# Main.net
KiCad netlist of a schematic drawn in EAGLE
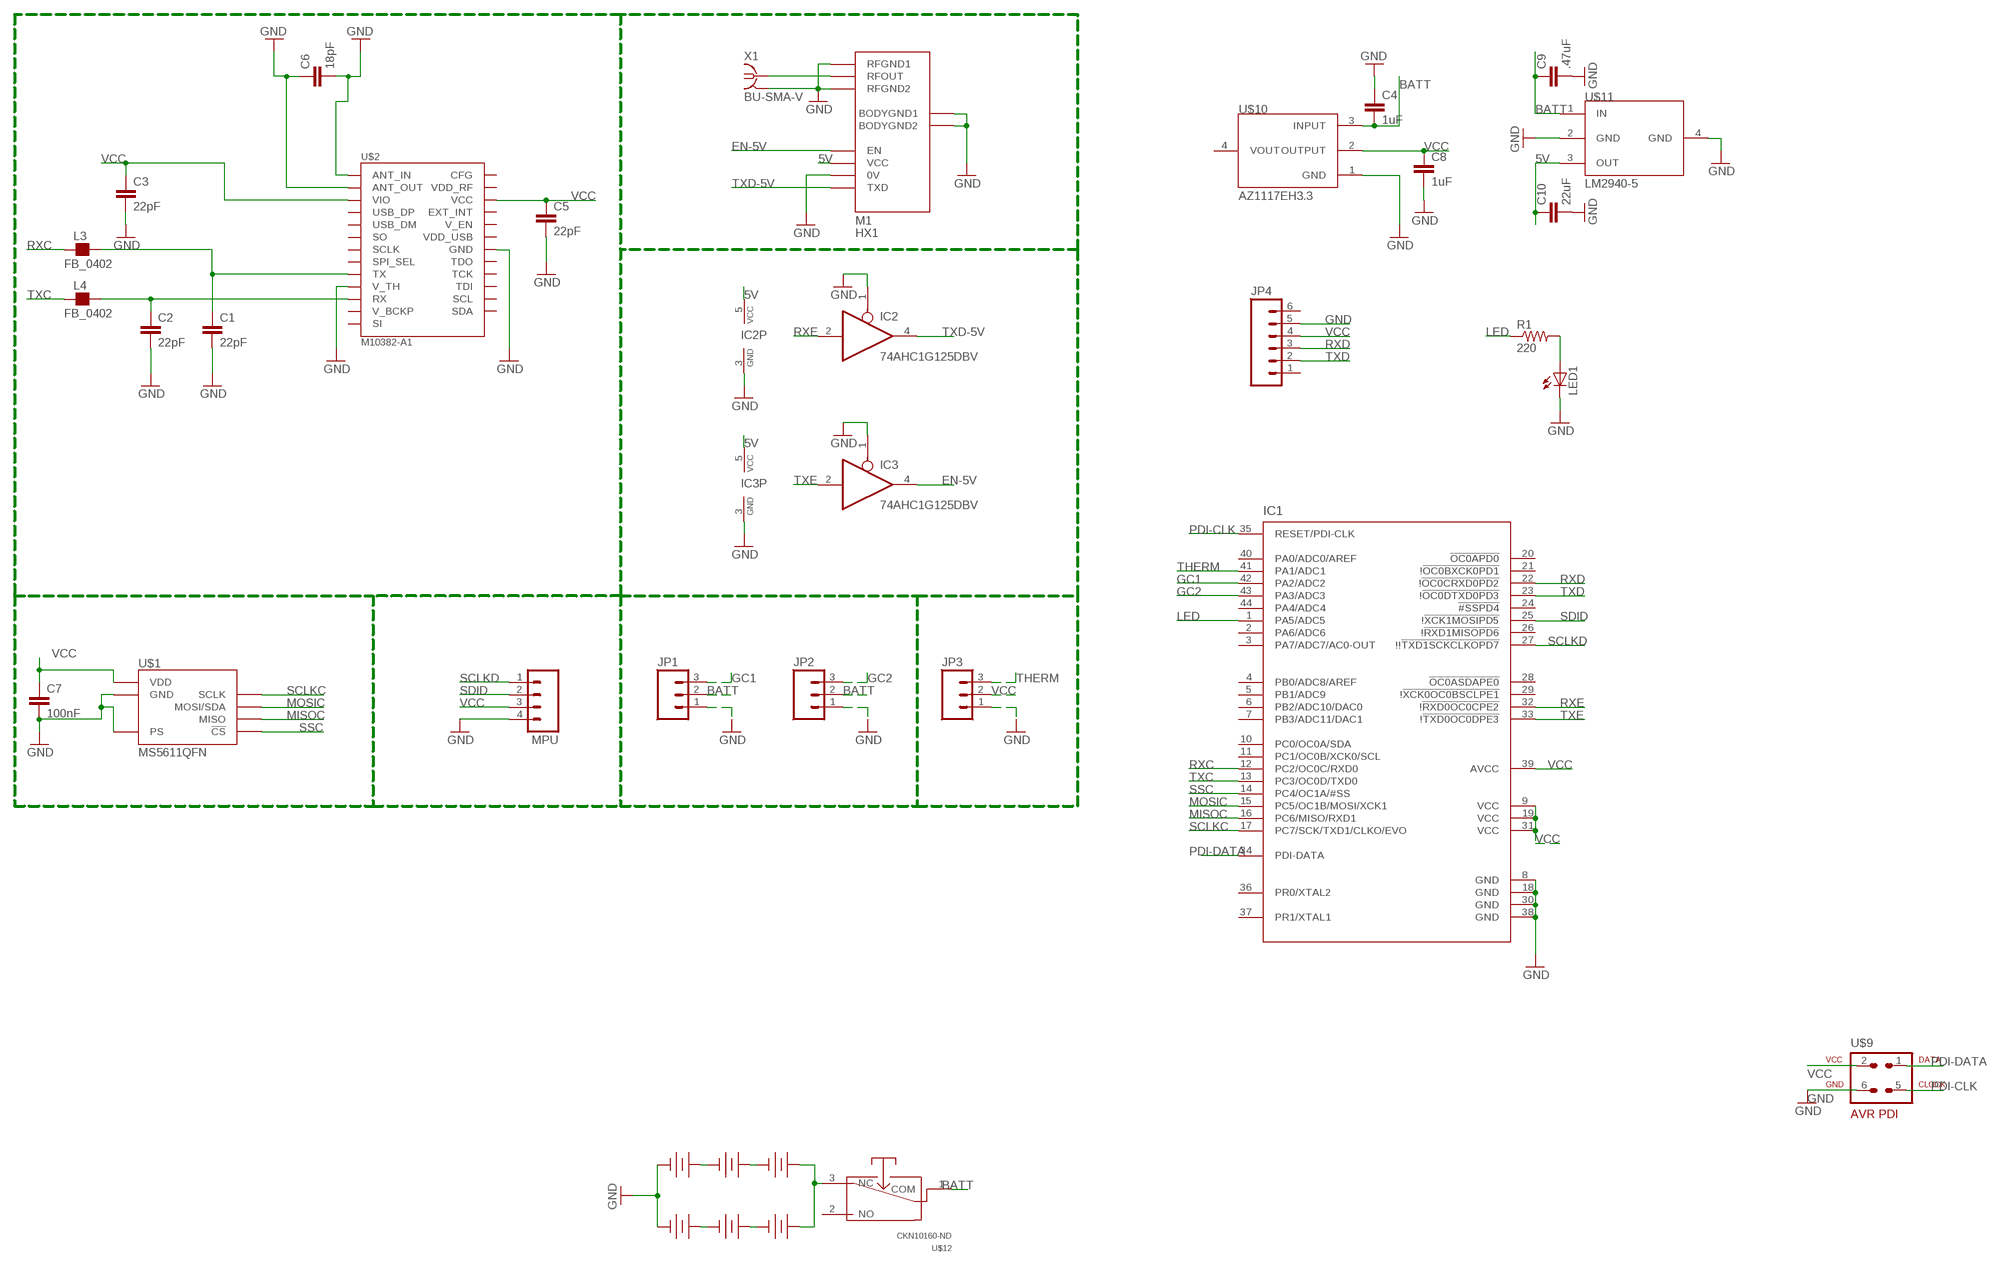
[diagram p0: schematic, sheet 1]

(export (version "E")
  (design (tool "Eeschema 10.0.6"))
  (components
    (comp (ref "C1")
      (value "22pF")
      (footprint "eagle-import:0805")
      (libsource (lib "eagle-import") (part "CAP0805"))
    )
    (comp (ref "C2")
      (value "22pF")
      (footprint "eagle-import:0805")
      (libsource (lib "eagle-import") (part "CAP0805"))
    )
    (comp (ref "C3")
      (value "22pF")
      (footprint "eagle-import:0805")
      (libsource (lib "eagle-import") (part "CAP0805"))
    )
    (comp (ref "C4")
      (value "1uF")
      (footprint "eagle-import:0603-CAP")
      (libsource (lib "eagle-import") (part "CAP0603-CAP"))
    )
    (comp (ref "C5")
      (value "22pF")
      (footprint "eagle-import:0805")
      (libsource (lib "eagle-import") (part "CAP0805"))
    )
    (comp (ref "C6")
      (value "18pF")
      (footprint "eagle-import:0805")
      (libsource (lib "eagle-import") (part "CAP0805"))
    )
    (comp (ref "C7")
      (value "100nF")
      (footprint "eagle-import:0805")
      (libsource (lib "eagle-import") (part "CAP0805"))
    )
    (comp (ref "C8")
      (value "1uF")
      (footprint "eagle-import:0603-CAP")
      (libsource (lib "eagle-import") (part "CAP0603-CAP"))
    )
    (comp (ref "C9")
      (value ".47uF")
      (footprint "eagle-import:0603-CAP")
      (libsource (lib "eagle-import") (part "CAP0603-CAP"))
    )
    (comp (ref "C10")
      (value "22uF")
      (footprint "eagle-import:0603-CAP")
      (libsource (lib "eagle-import") (part "CAP0603-CAP"))
    )
    (comp (ref "IC1")
      (value "AT-XMEGA-XXA4-AU")
      (footprint "eagle-import:QFP80P1200X1200X120-44N")
      (libsource (lib "eagle-import") (part "AT-XMEGA-XXA4-AU"))
    )
    (comp (ref "IC2")
      (value "74AHC1G125DBV")
      (footprint "eagle-import:SOT23-5")
      (libsource (lib "eagle-import") (part "741G125DBVAHC"))
    )
    (comp (ref "IC3")
      (value "74AHC1G125DBV")
      (footprint "eagle-import:SOT23-5")
      (libsource (lib "eagle-import") (part "741G125DBVAHC"))
    )
    (comp (ref "JP1")
      (value "M03JST-PTH")
      (footprint "eagle-import:JST-3-PTH")
      (libsource (lib "eagle-import") (part "M03JST-PTH"))
    )
    (comp (ref "JP2")
      (value "M03JST-PTH")
      (footprint "eagle-import:JST-3-PTH")
      (libsource (lib "eagle-import") (part "M03JST-PTH"))
    )
    (comp (ref "JP3")
      (value "M03JST-PTH")
      (footprint "eagle-import:JST-3-PTH")
      (libsource (lib "eagle-import") (part "M03JST-PTH"))
    )
    (comp (ref "JP4")
      (value "M06POLAR")
      (footprint "eagle-import:MOLEX-1X6")
      (libsource (lib "eagle-import") (part "M06POLAR"))
    )
    (comp (ref "L3")
      (value "FB_0402")
      (footprint "eagle-import:L0402")
      (libsource (lib "eagle-import") (part "FB_0402"))
    )
    (comp (ref "L4")
      (value "FB_0402")
      (footprint "eagle-import:L0402")
      (libsource (lib "eagle-import") (part "FB_0402"))
    )
    (comp (ref "LED1")
      (value "LEDCHIP-LED0603")
      (footprint "eagle-import:CHIP-LED0603")
      (libsource (lib "eagle-import") (part "LEDCHIP-LED0603"))
    )
    (comp (ref "M1")
      (value "HX1")
      (footprint "eagle-import:HX1")
      (libsource (lib "eagle-import") (part "HX1"))
    )
    (comp (ref "MPU")
      (value "M04")
      (footprint "eagle-import:04P")
      (libsource (lib "eagle-import") (part "M04"))
    )
    (comp (ref "R1")
      (value "220")
      (footprint "eagle-import:R0603")
      (libsource (lib "eagle-import") (part "R-US_R0603"))
    )
    (comp (ref "U$1")
      (value "MS5611QFN")
      (footprint "eagle-import:MS5611-01BA01")
      (libsource (lib "eagle-import") (part "MS5611QFN"))
    )
    (comp (ref "U$2")
      (value "M10382-A1")
      (footprint "eagle-import:M10382-A1")
      (libsource (lib "eagle-import") (part "M10382-A1"))
    )
    (comp (ref "U$3")
      (value "123_BATTERY_HOLDERCR-123-A")
      (footprint "eagle-import:CR-123-A_HOLDER")
      (libsource (lib "eagle-import") (part "123_BATTERY_HOLDERCR-123-A"))
    )
    (comp (ref "U$4")
      (value "123_BATTERY_HOLDERCR-123-A")
      (footprint "eagle-import:CR-123-A_HOLDER")
      (libsource (lib "eagle-import") (part "123_BATTERY_HOLDERCR-123-A"))
    )
    (comp (ref "U$5")
      (value "123_BATTERY_HOLDERCR-123-A")
      (footprint "eagle-import:CR-123-A_HOLDER")
      (libsource (lib "eagle-import") (part "123_BATTERY_HOLDERCR-123-A"))
    )
    (comp (ref "U$6")
      (value "123_BATTERY_HOLDERCR-123-A")
      (footprint "eagle-import:CR-123-A_HOLDER")
      (libsource (lib "eagle-import") (part "123_BATTERY_HOLDERCR-123-A"))
    )
    (comp (ref "U$7")
      (value "123_BATTERY_HOLDERCR-123-A")
      (footprint "eagle-import:CR-123-A_HOLDER")
      (libsource (lib "eagle-import") (part "123_BATTERY_HOLDERCR-123-A"))
    )
    (comp (ref "U$8")
      (value "123_BATTERY_HOLDERCR-123-A")
      (footprint "eagle-import:CR-123-A_HOLDER")
      (libsource (lib "eagle-import") (part "123_BATTERY_HOLDERCR-123-A"))
    )
    (comp (ref "U$9")
      (value "AVR-PDIVERT")
      (footprint "eagle-import:AVR-ISP-6")
      (libsource (lib "eagle-import") (part "AVR-PDIVERT"))
    )
    (comp (ref "U$10")
      (value "AZ1117EH3.3")
      (footprint "eagle-import:SOT-223")
      (libsource (lib "eagle-import") (part "AZ1117EH3.3"))
    )
    (comp (ref "U$11")
      (value "LM2940-5")
      (footprint "eagle-import:SOT-223")
      (libsource (lib "eagle-import") (part "LM2940-5"))
    )
    (comp (ref "U$12")
      (value "CKN10160-ND")
      (footprint "eagle-import:ZMCHFL3R")
      (libsource (lib "eagle-import") (part "CKN10160-ND"))
    )
    (comp (ref "X1")
      (value "BU-SMA-V")
      (footprint "eagle-import:BU-SMA-V")
      (libsource (lib "eagle-import") (part "BU-SMA-V"))
    )
  )
  (nets
    (net (code "1") (name "/5V") (class "Default")
      (node (ref "C10") (pin "1") (pinfunction "1_1") (pintype "passive"))
      (node (ref "IC2") (pin "5") (pinfunction "VCC_5") (pintype "power_in"))
      (node (ref "IC3") (pin "5") (pinfunction "VCC_5") (pintype "power_in"))
      (node (ref "M1") (pin "VCC") (pinfunction "VCC_VCC") (pintype "bidirectional"))
      (node (ref "U$11") (pin "3") (pinfunction "OUT_3") (pintype "bidirectional"))
    )
    (net (code "2") (name "/BATT") (class "Default")
      (node (ref "C4") (pin "2") (pinfunction "2_2") (pintype "passive"))
      (node (ref "C9") (pin "1") (pinfunction "1_1") (pintype "passive"))
      (node (ref "JP1") (pin "2") (pinfunction "2_2") (pintype "passive"))
      (node (ref "JP2") (pin "2") (pinfunction "2_2") (pintype "passive"))
      (node (ref "U$10") (pin "3") (pinfunction "INPUT_3") (pintype "bidirectional"))
      (node (ref "U$11") (pin "1") (pinfunction "IN_1") (pintype "bidirectional"))
      (node (ref "U$12") (pin "1") (pinfunction "COM_1") (pintype "bidirectional"))
    )
    (net (code "3") (name "/EN-5V") (class "Default")
      (node (ref "IC3") (pin "4") (pinfunction "O_4") (pintype "tri_state"))
      (node (ref "M1") (pin "EN") (pinfunction "EN_EN") (pintype "bidirectional"))
    )
    (net (code "4") (name "/GC1") (class "Default")
      (node (ref "IC1") (pin "42") (pinfunction "PA2/ADC2_42") (pintype "bidirectional"))
      (node (ref "JP1") (pin "3") (pinfunction "3_3") (pintype "passive"))
    )
    (net (code "5") (name "/GC2") (class "Default")
      (node (ref "IC1") (pin "43") (pinfunction "PA3/ADC3_43") (pintype "bidirectional"))
      (node (ref "JP2") (pin "3") (pinfunction "3_3") (pintype "passive"))
    )
    (net (code "6") (name "/LED") (class "Default")
      (node (ref "IC1") (pin "1") (pinfunction "PA5/ADC5_1") (pintype "bidirectional"))
      (node (ref "R1") (pin "1") (pinfunction "1_1") (pintype "passive"))
    )
    (net (code "7") (name "/MISOC") (class "Default")
      (node (ref "IC1") (pin "16") (pinfunction "PC6/MISO/RXD1_16") (pintype "bidirectional"))
      (node (ref "U$1") (pin "6") (pinfunction "MISO_6") (pintype "bidirectional"))
    )
    (net (code "8") (name "/MOSIC") (class "Default")
      (node (ref "IC1") (pin "15") (pinfunction "PC5/OC1B/MOSI/XCK1_15") (pintype "bidirectional"))
      (node (ref "U$1") (pin "7") (pinfunction "MOSI/SDA_7") (pintype "bidirectional"))
    )
    (net (code "9") (name "/PDI-CLK") (class "Default")
      (node (ref "IC1") (pin "35") (pinfunction "RESET/PDI-CLK_35") (pintype "input"))
      (node (ref "U$9") (pin "5") (pinfunction "5_5") (pintype "passive"))
    )
    (net (code "10") (name "/PDI-DATA") (class "Default")
      (node (ref "IC1") (pin "34") (pinfunction "PDI-DATA_34") (pintype "bidirectional"))
      (node (ref "U$9") (pin "1") (pinfunction "1_1") (pintype "passive"))
    )
    (net (code "11") (name "/RXC") (class "Default")
      (node (ref "IC1") (pin "12") (pinfunction "PC2/OC0C/RXD0_12") (pintype "bidirectional"))
      (node (ref "L3") (pin "1") (pinfunction "1_1") (pintype "passive"))
    )
    (net (code "12") (name "/RXD") (class "Default")
      (node (ref "IC1") (pin "22") (pinfunction "~OC0CRXD0PD2_22") (pintype "bidirectional"))
      (node (ref "JP4") (pin "3") (pinfunction "3_3") (pintype "passive"))
    )
    (net (code "13") (name "/RXE") (class "Default")
      (node (ref "IC1") (pin "32") (pinfunction "~RXD0OC0CPE2_32") (pintype "bidirectional"))
      (node (ref "IC2") (pin "2") (pinfunction "I_2") (pintype "input"))
    )
    (net (code "14") (name "/SCLKC") (class "Default")
      (node (ref "IC1") (pin "17") (pinfunction "PC7/SCK/TXD1/CLKO/EVO_17") (pintype "bidirectional"))
      (node (ref "U$1") (pin "8") (pinfunction "SCLK_8") (pintype "bidirectional"))
    )
    (net (code "15") (name "/SCLKD") (class "Default")
      (node (ref "IC1") (pin "27") (pinfunction "~~{TXD1SCKCLKOPD7}_27") (pintype "bidirectional"))
      (node (ref "MPU") (pin "1") (pinfunction "1_1") (pintype "passive"))
    )
    (net (code "16") (name "/SDID") (class "Default")
      (node (ref "IC1") (pin "25") (pinfunction "~XCK1MOSIPD5_25") (pintype "bidirectional"))
      (node (ref "MPU") (pin "2") (pinfunction "2_2") (pintype "passive"))
    )
    (net (code "17") (name "/SSC") (class "Default")
      (node (ref "IC1") (pin "14") (pinfunction "PC4/OC1A/#SS_14") (pintype "bidirectional"))
      (node (ref "U$1") (pin "4") (pinfunction "~{CS}_4") (pintype "bidirectional"))
      (node (ref "U$1") (pin "5") (pinfunction "~{CS}_5") (pintype "bidirectional"))
    )
    (net (code "18") (name "/THERM") (class "Default")
      (node (ref "IC1") (pin "41") (pinfunction "PA1/ADC1_41") (pintype "bidirectional"))
      (node (ref "JP3") (pin "3") (pinfunction "3_3") (pintype "passive"))
    )
    (net (code "19") (name "/TXC") (class "Default")
      (node (ref "IC1") (pin "13") (pinfunction "PC3/OC0D/TXD0_13") (pintype "bidirectional"))
      (node (ref "L4") (pin "1") (pinfunction "1_1") (pintype "passive"))
    )
    (net (code "20") (name "/TXD") (class "Default")
      (node (ref "IC1") (pin "23") (pinfunction "~OC0DTXD0PD3_23") (pintype "bidirectional"))
      (node (ref "JP4") (pin "2") (pinfunction "2_2") (pintype "passive"))
    )
    (net (code "21") (name "/TXD-5V") (class "Default")
      (node (ref "IC2") (pin "4") (pinfunction "O_4") (pintype "tri_state"))
      (node (ref "M1") (pin "TXD") (pinfunction "TXD_TXD") (pintype "bidirectional"))
    )
    (net (code "22") (name "/TXE") (class "Default")
      (node (ref "IC1") (pin "33") (pinfunction "~TXD0OC0DPE3_33") (pintype "bidirectional"))
      (node (ref "IC3") (pin "2") (pinfunction "I_2") (pintype "input"))
    )
    (net (code "23") (name "/VCC") (class "Default")
      (node (ref "C3") (pin "1") (pinfunction "1_1") (pintype "passive"))
      (node (ref "C5") (pin "1") (pinfunction "1_1") (pintype "passive"))
      (node (ref "C7") (pin "1") (pinfunction "1_1") (pintype "passive"))
      (node (ref "C8") (pin "1") (pinfunction "1_1") (pintype "passive"))
      (node (ref "IC1") (pin "19") (pinfunction "VCC_19") (pintype "power_in"))
      (node (ref "IC1") (pin "31") (pinfunction "VCC_31") (pintype "power_in"))
      (node (ref "IC1") (pin "39") (pinfunction "AVCC_39") (pintype "power_in"))
      (node (ref "IC1") (pin "9") (pinfunction "VCC_9") (pintype "power_in"))
      (node (ref "JP3") (pin "2") (pinfunction "2_2") (pintype "passive"))
      (node (ref "JP4") (pin "4") (pinfunction "4_4") (pintype "passive"))
      (node (ref "MPU") (pin "3") (pinfunction "3_3") (pintype "passive"))
      (node (ref "U$1") (pin "1") (pinfunction "VDD_1") (pintype "bidirectional"))
      (node (ref "U$10") (pin "2") (pinfunction "OUTPUT_2") (pintype "bidirectional"))
      (node (ref "U$2") (pin "27") (pinfunction "VCC_27") (pintype "bidirectional"))
      (node (ref "U$2") (pin "5") (pinfunction "VIO_5") (pintype "bidirectional"))
      (node (ref "U$9") (pin "2") (pinfunction "2_2") (pintype "passive"))
    )
    (net (code "24") (name "GND") (class "Default")
      (node (ref "C1") (pin "2") (pinfunction "2_2") (pintype "passive"))
      (node (ref "C10") (pin "2") (pinfunction "2_2") (pintype "passive"))
      (node (ref "C2") (pin "2") (pinfunction "2_2") (pintype "passive"))
      (node (ref "C3") (pin "2") (pinfunction "2_2") (pintype "passive"))
      (node (ref "C4") (pin "1") (pinfunction "1_1") (pintype "passive"))
      (node (ref "C5") (pin "2") (pinfunction "2_2") (pintype "passive"))
      (node (ref "C6") (pin "1") (pinfunction "1_1") (pintype "passive"))
      (node (ref "C6") (pin "2") (pinfunction "2_2") (pintype "passive"))
      (node (ref "C7") (pin "2") (pinfunction "2_2") (pintype "passive"))
      (node (ref "C8") (pin "2") (pinfunction "2_2") (pintype "passive"))
      (node (ref "C9") (pin "2") (pinfunction "2_2") (pintype "passive"))
      (node (ref "IC1") (pin "18") (pinfunction "GND_18") (pintype "power_in"))
      (node (ref "IC1") (pin "30") (pinfunction "GND_30") (pintype "power_in"))
      (node (ref "IC1") (pin "38") (pinfunction "GND_38") (pintype "power_in"))
      (node (ref "IC1") (pin "8") (pinfunction "GND_8") (pintype "power_in"))
      (node (ref "IC2") (pin "1") (pinfunction "OE_1") (pintype "input"))
      (node (ref "IC2") (pin "3") (pinfunction "GND_3") (pintype "power_in"))
      (node (ref "IC3") (pin "1") (pinfunction "OE_1") (pintype "input"))
      (node (ref "IC3") (pin "3") (pinfunction "GND_3") (pintype "power_in"))
      (node (ref "JP1") (pin "1") (pinfunction "1_1") (pintype "passive"))
      (node (ref "JP2") (pin "1") (pinfunction "1_1") (pintype "passive"))
      (node (ref "JP3") (pin "1") (pinfunction "1_1") (pintype "passive"))
      (node (ref "JP4") (pin "5") (pinfunction "5_5") (pintype "passive"))
      (node (ref "LED1") (pin "C") (pinfunction "C_C") (pintype "passive"))
      (node (ref "M1") (pin "0V") (pinfunction "0V_0V") (pintype "bidirectional"))
      (node (ref "M1") (pin "BODYGND1") (pinfunction "BODYGND1_BODYGND1") (pintype "bidirectional"))
      (node (ref "M1") (pin "BODYGND2") (pinfunction "BODYGND2_BODYGND2") (pintype "bidirectional"))
      (node (ref "M1") (pin "RFGND1") (pinfunction "RFGND1_RFGND1") (pintype "bidirectional"))
      (node (ref "M1") (pin "RFGND2") (pinfunction "RFGND2_RFGND2") (pintype "bidirectional"))
      (node (ref "MPU") (pin "4") (pinfunction "4_4") (pintype "passive"))
      (node (ref "U$1") (pin "2") (pinfunction "PS_2") (pintype "bidirectional"))
      (node (ref "U$1") (pin "3") (pinfunction "GND_3") (pintype "bidirectional"))
      (node (ref "U$10") (pin "1") (pinfunction "GND_1") (pintype "bidirectional"))
      (node (ref "U$11") (pin "2") (pinfunction "GND_2") (pintype "bidirectional"))
      (node (ref "U$11") (pin "4") (pinfunction "GND_4") (pintype "bidirectional"))
      (node (ref "U$2") (pin "1") (pinfunction "ANT_IN_1") (pintype "bidirectional"))
      (node (ref "U$2") (pin "12") (pinfunction "V_TH_12") (pintype "bidirectional"))
      (node (ref "U$2") (pin "14") (pinfunction "GND_14") (pintype "bidirectional"))
      (node (ref "U$2") (pin "17") (pinfunction "GND_17") (pintype "bidirectional"))
      (node (ref "U$2") (pin "2") (pinfunction "GND_2") (pintype "bidirectional"))
      (node (ref "U$2") (pin "21") (pinfunction "GND_21") (pintype "bidirectional"))
      (node (ref "U$2") (pin "24") (pinfunction "GND_24") (pintype "bidirectional"))
      (node (ref "U$2") (pin "26") (pinfunction "GND_26") (pintype "bidirectional"))
      (node (ref "U$2") (pin "28") (pinfunction "GND_28") (pintype "bidirectional"))
      (node (ref "U$2") (pin "3") (pinfunction "ANT_OUT_3") (pintype "bidirectional"))
      (node (ref "U$2") (pin "33") (pinfunction "GND_33") (pintype "bidirectional"))
      (node (ref "U$2") (pin "34") (pinfunction "GND_34") (pintype "bidirectional"))
      (node (ref "U$2") (pin "35") (pinfunction "GND_35") (pintype "bidirectional"))
      (node (ref "U$2") (pin "36") (pinfunction "GND_36") (pintype "bidirectional"))
      (node (ref "U$2") (pin "4") (pinfunction "GND_4") (pintype "bidirectional"))
      (node (ref "U$3") (pin "-") (pinfunction "-_-") (pintype "bidirectional"))
      (node (ref "U$6") (pin "-") (pinfunction "-_-") (pintype "bidirectional"))
      (node (ref "U$9") (pin "6") (pinfunction "6_6") (pintype "passive"))
      (node (ref "X1") (pin "2") (pinfunction "GND_2") (pintype "power_in"))
    )
    (net (code "25") (name "Net-(LED1-PadA)") (class "Default")
      (node (ref "LED1") (pin "A") (pinfunction "A_A") (pintype "passive"))
      (node (ref "R1") (pin "2") (pinfunction "2_2") (pintype "passive"))
    )
    (net (code "26") (name "Net-(M1-PadRFOUT)") (class "Default")
      (node (ref "M1") (pin "RFOUT") (pinfunction "RFOUT_RFOUT") (pintype "bidirectional"))
      (node (ref "X1") (pin "1") (pinfunction "1_1") (pintype "passive"))
    )
    (net (code "27") (name "Net-(U$2-RX)") (class "Default")
      (node (ref "C2") (pin "1") (pinfunction "1_1") (pintype "passive"))
      (node (ref "L4") (pin "2") (pinfunction "2_2") (pintype "passive"))
      (node (ref "U$2") (pin "13") (pinfunction "RX_13") (pintype "bidirectional"))
    )
    (net (code "28") (name "Net-(U$2-TX)") (class "Default")
      (node (ref "C1") (pin "1") (pinfunction "1_1") (pintype "passive"))
      (node (ref "L3") (pin "2") (pinfunction "2_2") (pintype "passive"))
      (node (ref "U$2") (pin "11") (pinfunction "TX_11") (pintype "bidirectional"))
    )
    (net (code "29") (name "Net-(U$3-Pad+)") (class "Default")
      (node (ref "U$3") (pin "+") (pinfunction "+_+") (pintype "bidirectional"))
      (node (ref "U$4") (pin "-") (pinfunction "-_-") (pintype "bidirectional"))
    )
    (net (code "30") (name "Net-(U$4-Pad+)") (class "Default")
      (node (ref "U$4") (pin "+") (pinfunction "+_+") (pintype "bidirectional"))
      (node (ref "U$5") (pin "-") (pinfunction "-_-") (pintype "bidirectional"))
    )
    (net (code "31") (name "Net-(U$6-Pad+)") (class "Default")
      (node (ref "U$6") (pin "+") (pinfunction "+_+") (pintype "bidirectional"))
      (node (ref "U$7") (pin "-") (pinfunction "-_-") (pintype "bidirectional"))
    )
    (net (code "32") (name "Net-(U$7-Pad+)") (class "Default")
      (node (ref "U$7") (pin "+") (pinfunction "+_+") (pintype "bidirectional"))
      (node (ref "U$8") (pin "-") (pinfunction "-_-") (pintype "bidirectional"))
    )
    (net (code "33") (name "Net-(U$12-NC)") (class "Default")
      (node (ref "U$12") (pin "3") (pinfunction "NC_3") (pintype "bidirectional"))
      (node (ref "U$5") (pin "+") (pinfunction "+_+") (pintype "bidirectional"))
      (node (ref "U$8") (pin "+") (pinfunction "+_+") (pintype "bidirectional"))
    )
    (net (code "34") (name "unconnected-(IC1-PA0{slash}ADC0{slash}AREF-Pad40)") (class "Default")
      (node (ref "IC1") (pin "40") (pinfunction "PA0/ADC0/AREF_40") (pintype "bidirectional"))
    )
    (net (code "35") (name "unconnected-(IC1-PA4{slash}ADC4-Pad44)") (class "Default")
      (node (ref "IC1") (pin "44") (pinfunction "PA4/ADC4_44") (pintype "bidirectional"))
    )
    (net (code "36") (name "unconnected-(IC1-PA6{slash}ADC6-Pad2)") (class "Default")
      (node (ref "IC1") (pin "2") (pinfunction "PA6/ADC6_2") (pintype "bidirectional"))
    )
    (net (code "37") (name "unconnected-(IC1-PA7{slash}ADC7{slash}AC0-OUT-Pad3)") (class "Default")
      (node (ref "IC1") (pin "3") (pinfunction "PA7/ADC7/AC0-OUT_3") (pintype "bidirectional"))
    )
    (net (code "38") (name "unconnected-(IC1-PB0{slash}ADC8{slash}AREF-Pad4)") (class "Default")
      (node (ref "IC1") (pin "4") (pinfunction "PB0/ADC8/AREF_4") (pintype "bidirectional"))
    )
    (net (code "39") (name "unconnected-(IC1-PB1{slash}ADC9-Pad5)") (class "Default")
      (node (ref "IC1") (pin "5") (pinfunction "PB1/ADC9_5") (pintype "bidirectional"))
    )
    (net (code "40") (name "unconnected-(IC1-PB2{slash}ADC10{slash}DAC0-Pad6)") (class "Default")
      (node (ref "IC1") (pin "6") (pinfunction "PB2/ADC10/DAC0_6") (pintype "bidirectional"))
    )
    (net (code "41") (name "unconnected-(IC1-PB3{slash}ADC11{slash}DAC1-Pad7)") (class "Default")
      (node (ref "IC1") (pin "7") (pinfunction "PB3/ADC11/DAC1_7") (pintype "bidirectional"))
    )
    (net (code "42") (name "unconnected-(IC1-PC0{slash}OC0A{slash}SDA-Pad10)") (class "Default")
      (node (ref "IC1") (pin "10") (pinfunction "PC0/OC0A/SDA_10") (pintype "bidirectional"))
    )
    (net (code "43") (name "unconnected-(IC1-PC1{slash}OC0B{slash}XCK0{slash}SCL-Pad11)") (class "Default")
      (node (ref "IC1") (pin "11") (pinfunction "PC1/OC0B/XCK0/SCL_11") (pintype "bidirectional"))
    )
    (net (code "44") (name "unconnected-(IC1-PR0{slash}XTAL2-Pad36)") (class "Default")
      (node (ref "IC1") (pin "36") (pinfunction "PR0/XTAL2_36") (pintype "bidirectional"))
    )
    (net (code "45") (name "unconnected-(IC1-PR1{slash}XTAL1-Pad37)") (class "Default")
      (node (ref "IC1") (pin "37") (pinfunction "PR1/XTAL1_37") (pintype "bidirectional"))
    )
    (net (code "46") (name "unconnected-(IC1-~OC0BXCK0PD1-Pad21)") (class "Default")
      (node (ref "IC1") (pin "21") (pinfunction "~OC0BXCK0PD1_21") (pintype "bidirectional"))
    )
    (net (code "47") (name "unconnected-(IC1-~RXD1MISOPD6-Pad26)") (class "Default")
      (node (ref "IC1") (pin "26") (pinfunction "~RXD1MISOPD6_26") (pintype "bidirectional"))
    )
    (net (code "48") (name "unconnected-(IC1-~XCK0OC0BSCLPE1-Pad29)") (class "Default")
      (node (ref "IC1") (pin "29") (pinfunction "~XCK0OC0BSCLPE1_29") (pintype "bidirectional"))
    )
    (net (code "49") (name "unconnected-(IC1-~{#SSPD4}-Pad24)") (class "Default")
      (node (ref "IC1") (pin "24") (pinfunction "~{#SSPD4}_24") (pintype "bidirectional"))
    )
    (net (code "50") (name "unconnected-(IC1-~{OC0APD0}-Pad20)") (class "Default")
      (node (ref "IC1") (pin "20") (pinfunction "~{OC0APD0}_20") (pintype "bidirectional"))
    )
    (net (code "51") (name "unconnected-(IC1-~{OC0ASDAPE0}-Pad28)") (class "Default")
      (node (ref "IC1") (pin "28") (pinfunction "~{OC0ASDAPE0}_28") (pintype "bidirectional"))
    )
    (net (code "52") (name "unconnected-(JP4-Pad1)") (class "Default")
      (node (ref "JP4") (pin "1") (pinfunction "1_1") (pintype "passive"))
    )
    (net (code "53") (name "unconnected-(JP4-Pad6)") (class "Default")
      (node (ref "JP4") (pin "6") (pinfunction "6_6") (pintype "passive"))
    )
    (net (code "54") (name "unconnected-(U$2-CFG-Pad31)") (class "Default")
      (node (ref "U$2") (pin "31") (pinfunction "CFG_31") (pintype "bidirectional"))
    )
    (net (code "55") (name "unconnected-(U$2-EXT_INT-Pad29)") (class "Default")
      (node (ref "U$2") (pin "29") (pinfunction "EXT_INT_29") (pintype "bidirectional"))
    )
    (net (code "56") (name "unconnected-(U$2-SCL-Pad19)") (class "Default")
      (node (ref "U$2") (pin "19") (pinfunction "SCL_19") (pintype "bidirectional"))
    )
    (net (code "57") (name "unconnected-(U$2-SCLK-Pad9)") (class "Default")
      (node (ref "U$2") (pin "9") (pinfunction "SCLK_9") (pintype "bidirectional"))
    )
    (net (code "58") (name "unconnected-(U$2-SDA-Pad18)") (class "Default")
      (node (ref "U$2") (pin "18") (pinfunction "SDA_18") (pintype "bidirectional"))
    )
    (net (code "59") (name "unconnected-(U$2-SI-Pad16)") (class "Default")
      (node (ref "U$2") (pin "16") (pinfunction "SI_16") (pintype "bidirectional"))
    )
    (net (code "60") (name "unconnected-(U$2-SO-Pad8)") (class "Default")
      (node (ref "U$2") (pin "8") (pinfunction "SO_8") (pintype "bidirectional"))
    )
    (net (code "61") (name "unconnected-(U$2-SPI_SEL-Pad10)") (class "Default")
      (node (ref "U$2") (pin "10") (pinfunction "SPI_SEL_10") (pintype "bidirectional"))
    )
    (net (code "62") (name "unconnected-(U$2-TCK-Pad22)") (class "Default")
      (node (ref "U$2") (pin "22") (pinfunction "TCK_22") (pintype "bidirectional"))
    )
    (net (code "63") (name "unconnected-(U$2-TDI-Pad20)") (class "Default")
      (node (ref "U$2") (pin "20") (pinfunction "TDI_20") (pintype "bidirectional"))
    )
    (net (code "64") (name "unconnected-(U$2-TDO-Pad23)") (class "Default")
      (node (ref "U$2") (pin "23") (pinfunction "TDO_23") (pintype "bidirectional"))
    )
    (net (code "65") (name "unconnected-(U$2-USB_DM-Pad7)") (class "Default")
      (node (ref "U$2") (pin "7") (pinfunction "USB_DM_7") (pintype "bidirectional"))
    )
    (net (code "66") (name "unconnected-(U$2-USB_DP-Pad6)") (class "Default")
      (node (ref "U$2") (pin "6") (pinfunction "USB_DP_6") (pintype "bidirectional"))
    )
    (net (code "67") (name "unconnected-(U$2-VDD_RF-Pad25)") (class "Default")
      (node (ref "U$2") (pin "25") (pinfunction "VDD_RF_25") (pintype "bidirectional"))
    )
    (net (code "68") (name "unconnected-(U$2-VDD_USB-Pad32)") (class "Default")
      (node (ref "U$2") (pin "32") (pinfunction "VDD_USB_32") (pintype "bidirectional"))
    )
    (net (code "69") (name "unconnected-(U$2-V_BCKP-Pad15)") (class "Default")
      (node (ref "U$2") (pin "15") (pinfunction "V_BCKP_15") (pintype "bidirectional"))
    )
    (net (code "70") (name "unconnected-(U$2-V_EN-Pad30)") (class "Default")
      (node (ref "U$2") (pin "30") (pinfunction "V_EN_30") (pintype "bidirectional"))
    )
    (net (code "71") (name "unconnected-(U$10-VOUT-Pad4)") (class "Default")
      (node (ref "U$10") (pin "4") (pinfunction "VOUT_4") (pintype "bidirectional"))
    )
    (net (code "72") (name "unconnected-(U$12-NO-Pad2)") (class "Default")
      (node (ref "U$12") (pin "2") (pinfunction "NO_2") (pintype "bidirectional"))
    )
  )
)
